# SCH_USB-hub_2024-05-28.net
KiCad netlist of a schematic drawn in EasyEDA
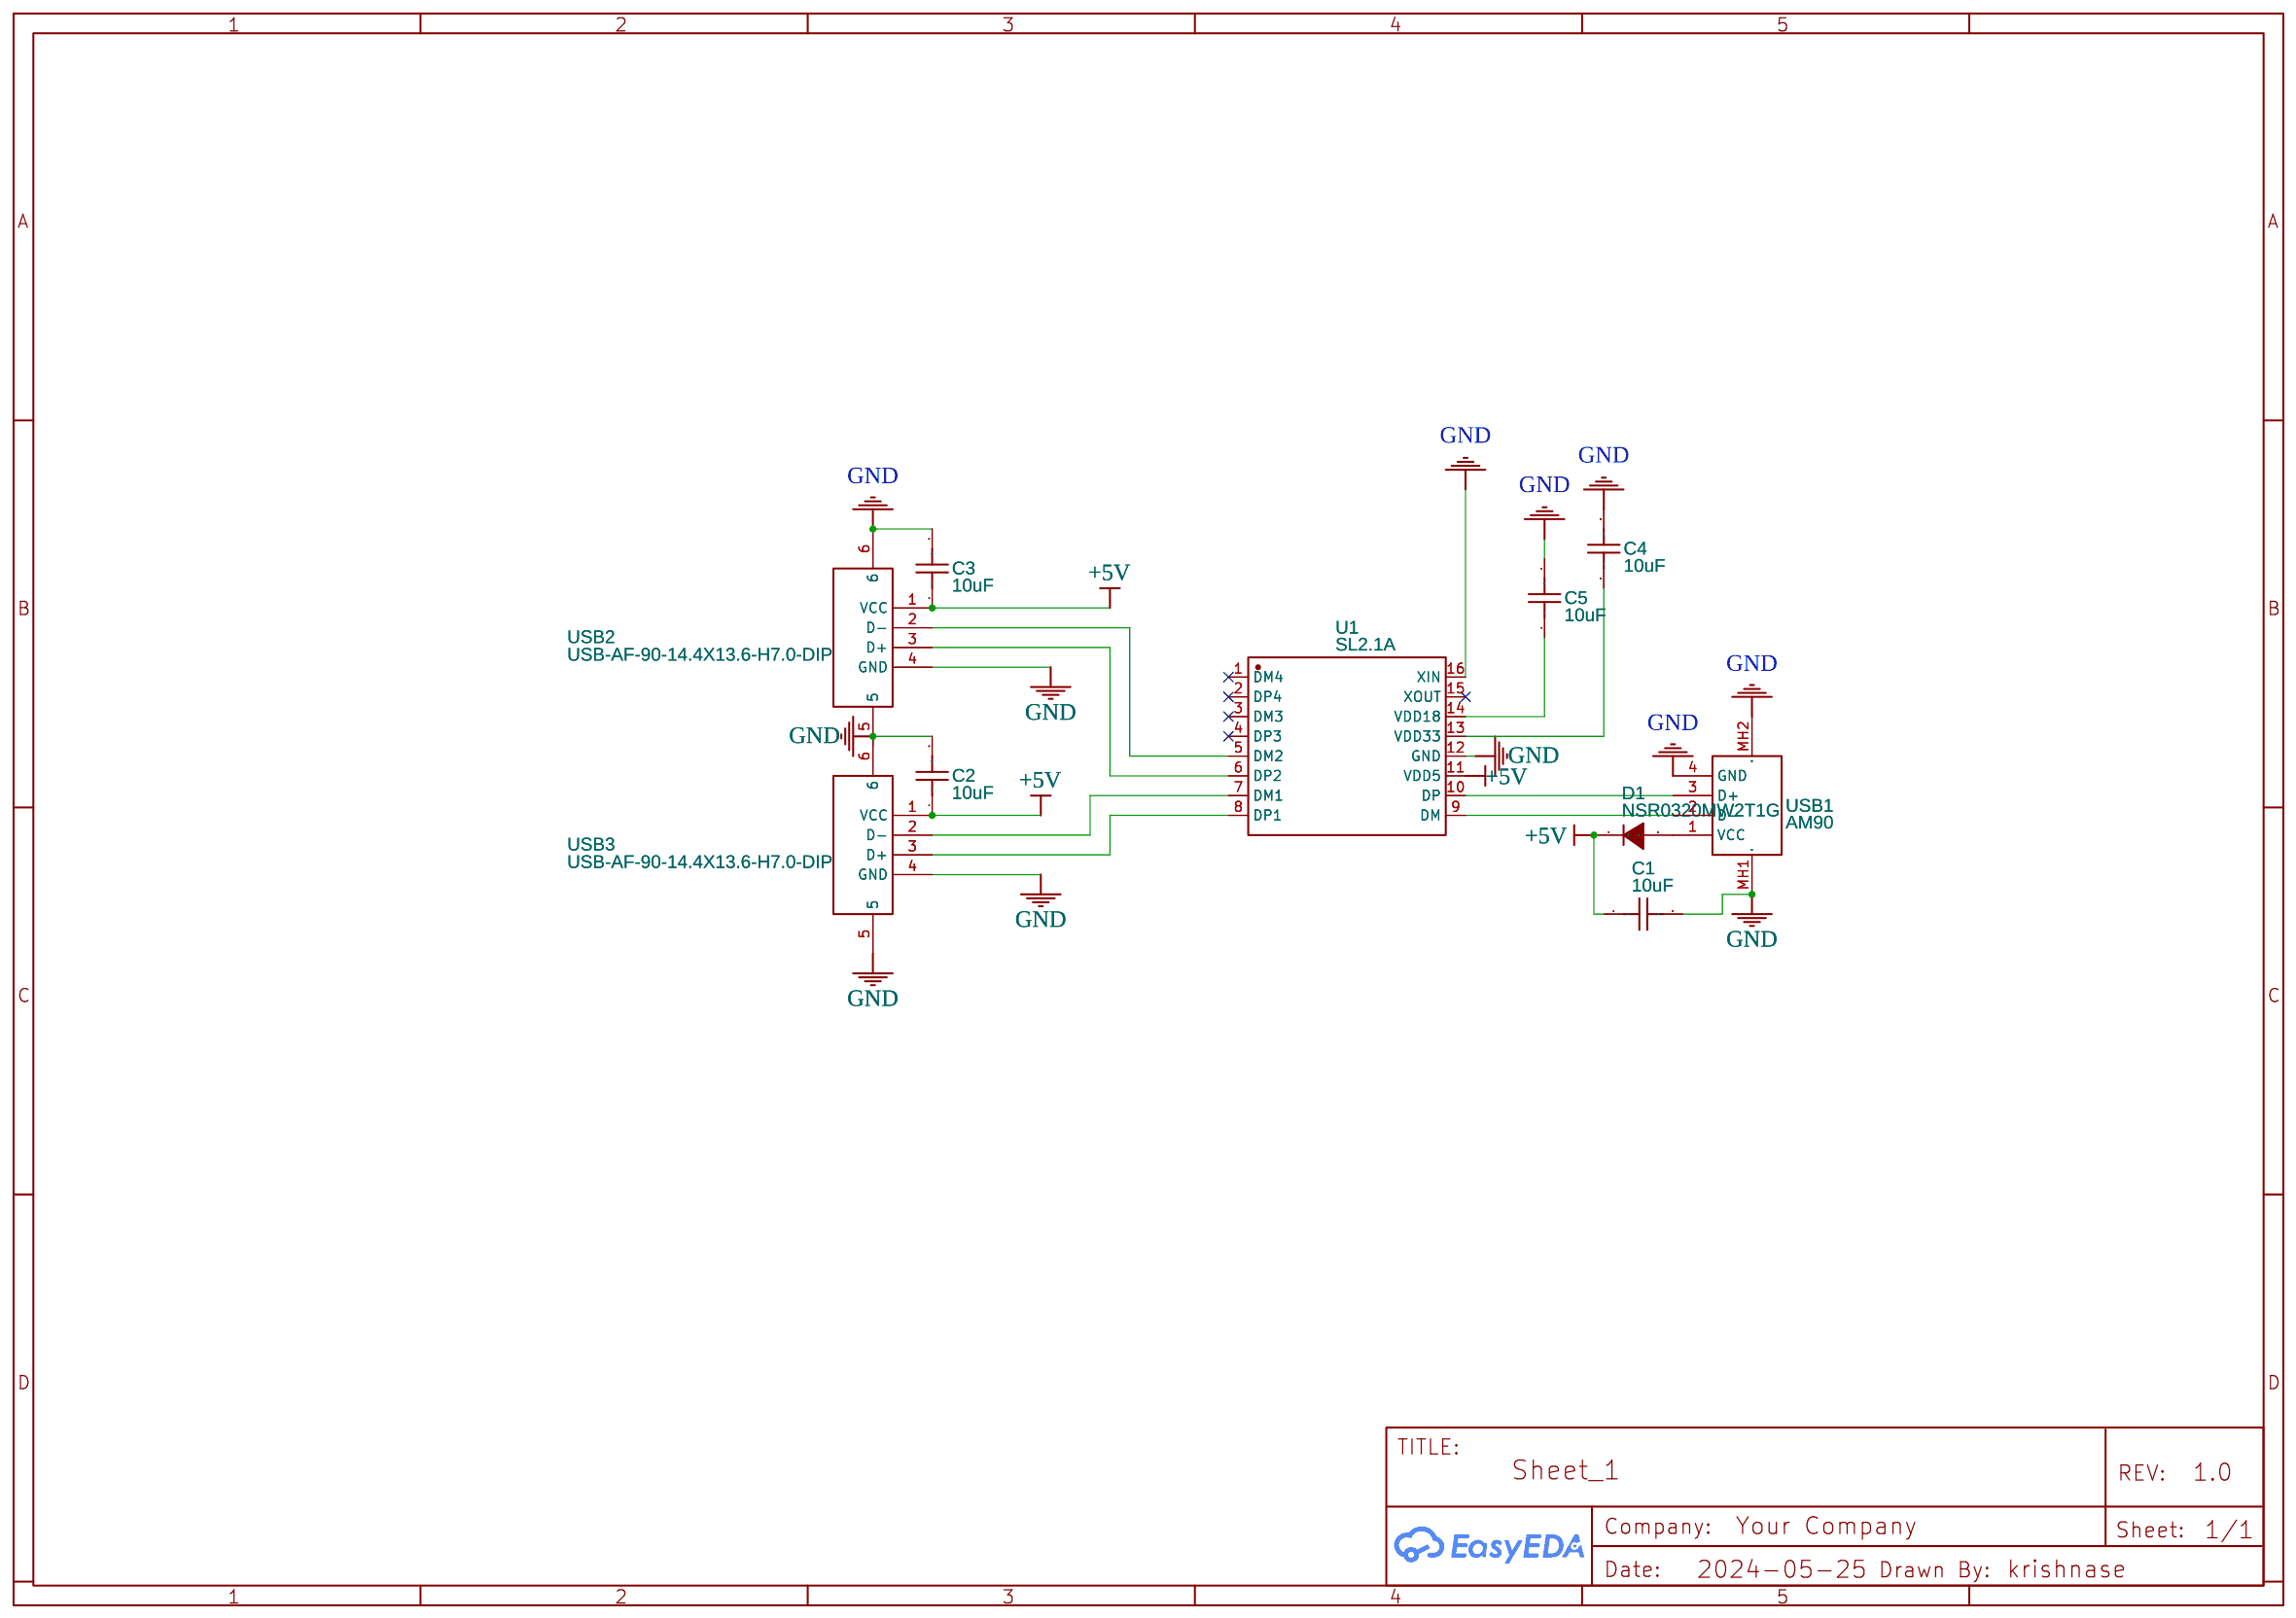
[diagram p0: schematic sheet]

(export (version "E")
  (design (tool "Eeschema 10.0.6"))
  (components
    (comp (ref "C1")
      (value "10uF")
      (fields
        (field (name "Manufacturer Part") "CL10A106KP8NNNC")
        (field (name "Manufacturer") "SAMSUNG(三星)")
      )
      (libsource (lib "") (part "CL10A106KP8NNNC_1"))
    )
    (comp (ref "C2")
      (value "10uF")
      (fields
        (field (name "Manufacturer Part") "CL10A106KP8NNNC")
        (field (name "Manufacturer") "SAMSUNG(三星)")
      )
      (libsource (lib "") (part "CL10A106KP8NNNC"))
    )
    (comp (ref "C3")
      (value "10uF")
      (fields
        (field (name "Manufacturer Part") "CL10A106KP8NNNC")
        (field (name "Manufacturer") "SAMSUNG(三星)")
      )
      (libsource (lib "") (part "CL10A106KP8NNNC"))
    )
    (comp (ref "C4")
      (value "10uF")
      (fields
        (field (name "Manufacturer Part") "CL10A106KP8NNNC")
        (field (name "Manufacturer") "SAMSUNG(三星)")
      )
      (libsource (lib "") (part "CL10A106KP8NNNC"))
    )
    (comp (ref "C5")
      (value "10uF")
      (fields
        (field (name "Manufacturer Part") "CL10A106KP8NNNC")
        (field (name "Manufacturer") "SAMSUNG(三星)")
      )
      (libsource (lib "") (part "CL10A106KP8NNNC"))
    )
    (comp (ref "D1")
      (value "NSR0320MW2T1G")
      (fields (field (name "Manufacturer") "onsemi(安森美)"))
      (libsource (lib "") (part "NSR0320MW2T1G"))
    )
    (comp (ref "U1")
      (value "SL2.1A")
      (fields (field (name "Manufacturer") "CoreChips(和芯润德)"))
      (libsource (lib "") (part "SL2.1A"))
    )
    (comp (ref "USB1")
      (value "AM90")
      (fields (field (name "Manufacturer") "SHOU HAN(首韩)"))
      (libsource (lib "") (part "AM90"))
    )
    (comp (ref "USB2")
      (value "USB-AF-90-14.4X13.6-H7.0-DIP")
      (fields (field (name "Manufacturer Part") "903-131A1011D10100") (field (name "Manufacturer") "精拓金"))
      (libsource (lib "") (part "USB-AF-90-14.4X13.6-H7.0-DIP"))
    )
    (comp (ref "USB3")
      (value "USB-AF-90-14.4X13.6-H7.0-DIP")
      (fields (field (name "Manufacturer Part") "903-131A1011D10100") (field (name "Manufacturer") "精拓金"))
      (libsource (lib "") (part "USB-AF-90-14.4X13.6-H7.0-DIP"))
    )
  )
  (nets
    (net (code "1") (name "+5V") (class "Default")
      (node (ref "C1") (pin "1") (pinfunction "1_1") (pintype "unspecified"))
      (node (ref "C2") (pin "1") (pinfunction "1_1") (pintype "unspecified"))
      (node (ref "C3") (pin "1") (pinfunction "1_1") (pintype "unspecified"))
      (node (ref "D1") (pin "1") (pinfunction "C_1") (pintype "unspecified"))
      (node (ref "U1") (pin "11") (pinfunction "VDD5_11") (pintype "unspecified"))
      (node (ref "USB2") (pin "1") (pinfunction "VCC_1") (pintype "unspecified"))
      (node (ref "USB3") (pin "1") (pinfunction "VCC_1") (pintype "unspecified"))
    )
    (net (code "2") (name "GND") (class "Default")
      (node (ref "C1") (pin "2") (pinfunction "2_2") (pintype "unspecified"))
      (node (ref "C2") (pin "2") (pinfunction "2_2") (pintype "unspecified"))
      (node (ref "C3") (pin "2") (pinfunction "2_2") (pintype "unspecified"))
      (node (ref "C4") (pin "2") (pinfunction "2_2") (pintype "unspecified"))
      (node (ref "C5") (pin "2") (pinfunction "2_2") (pintype "unspecified"))
      (node (ref "U1") (pin "12") (pinfunction "GND_12") (pintype "unspecified"))
      (node (ref "U1") (pin "16") (pinfunction "XIN_16") (pintype "unspecified"))
      (node (ref "USB1") (pin "4") (pinfunction "GND_4") (pintype "input"))
      (node (ref "USB1") (pin "MH1") (pinfunction "MH1_MH1") (pintype "unspecified"))
      (node (ref "USB1") (pin "MH2") (pinfunction "MH2_MH2") (pintype "unspecified"))
      (node (ref "USB2") (pin "4") (pinfunction "GND_4") (pintype "unspecified"))
      (node (ref "USB2") (pin "6") (pinfunction "6_6") (pintype "unspecified"))
      (node (ref "USB3") (pin "4") (pinfunction "GND_4") (pintype "unspecified"))
      (node (ref "USB3") (pin "5") (pinfunction "5_5") (pintype "unspecified"))
      (node (ref "USB3") (pin "6") (pinfunction "6_6") (pintype "unspecified"))
    )
    (net (code "3") (name "Net-(D1-A)") (class "Default")
      (node (ref "D1") (pin "2") (pinfunction "A_2") (pintype "unspecified"))
      (node (ref "USB1") (pin "1") (pinfunction "VCC_1") (pintype "input"))
    )
    (net (code "4") (name "Net-(U1-DM)") (class "Default")
      (node (ref "U1") (pin "9") (pinfunction "DM_9") (pintype "unspecified"))
      (node (ref "USB1") (pin "2") (pinfunction "D-_2") (pintype "input"))
    )
    (net (code "5") (name "Net-(U1-DM1)") (class "Default")
      (node (ref "U1") (pin "7") (pinfunction "DM1_7") (pintype "unspecified"))
      (node (ref "USB3") (pin "2") (pinfunction "D-_2") (pintype "unspecified"))
    )
    (net (code "6") (name "Net-(U1-DM2)") (class "Default")
      (node (ref "U1") (pin "5") (pinfunction "DM2_5") (pintype "unspecified"))
      (node (ref "USB2") (pin "2") (pinfunction "D-_2") (pintype "unspecified"))
    )
    (net (code "7") (name "Net-(U1-DP)") (class "Default")
      (node (ref "U1") (pin "10") (pinfunction "DP_10") (pintype "unspecified"))
      (node (ref "USB1") (pin "3") (pinfunction "D+_3") (pintype "input"))
    )
    (net (code "8") (name "Net-(U1-DP1)") (class "Default")
      (node (ref "U1") (pin "8") (pinfunction "DP1_8") (pintype "unspecified"))
      (node (ref "USB3") (pin "3") (pinfunction "D+_3") (pintype "unspecified"))
    )
    (net (code "9") (name "Net-(U1-DP2)") (class "Default")
      (node (ref "U1") (pin "6") (pinfunction "DP2_6") (pintype "unspecified"))
      (node (ref "USB2") (pin "3") (pinfunction "D+_3") (pintype "unspecified"))
    )
    (net (code "10") (name "Net-(U1-VDD18)") (class "Default")
      (node (ref "C5") (pin "1") (pinfunction "1_1") (pintype "unspecified"))
      (node (ref "U1") (pin "14") (pinfunction "VDD18_14") (pintype "unspecified"))
    )
    (net (code "11") (name "Net-(U1-VDD33)") (class "Default")
      (node (ref "C4") (pin "1") (pinfunction "1_1") (pintype "unspecified"))
      (node (ref "U1") (pin "13") (pinfunction "VDD33_13") (pintype "unspecified"))
    )
    (net (code "12") (name "unconnected-(U1-DM3-Pad3)") (class "Default")
      (node (ref "U1") (pin "3") (pinfunction "DM3_3") (pintype "unspecified+no_connect"))
    )
    (net (code "13") (name "unconnected-(U1-DM4-Pad1)") (class "Default")
      (node (ref "U1") (pin "1") (pinfunction "DM4_1") (pintype "unspecified+no_connect"))
    )
    (net (code "14") (name "unconnected-(U1-DP3-Pad4)") (class "Default")
      (node (ref "U1") (pin "4") (pinfunction "DP3_4") (pintype "unspecified+no_connect"))
    )
    (net (code "15") (name "unconnected-(U1-DP4-Pad2)") (class "Default")
      (node (ref "U1") (pin "2") (pinfunction "DP4_2") (pintype "unspecified+no_connect"))
    )
    (net (code "16") (name "unconnected-(U1-XOUT-Pad15)") (class "Default")
      (node (ref "U1") (pin "15") (pinfunction "XOUT_15") (pintype "unspecified+no_connect"))
    )
    (net (code "17") (name "unconnected-(USB2-Pad5)") (class "Default")
      (node (ref "USB2") (pin "5") (pinfunction "5_5") (pintype "unspecified"))
    )
  )
)
